# sonoff_DIY_3_gang_Dip_version-V_1_1.net
KiCad netlist of a schematic drawn in EAGLE
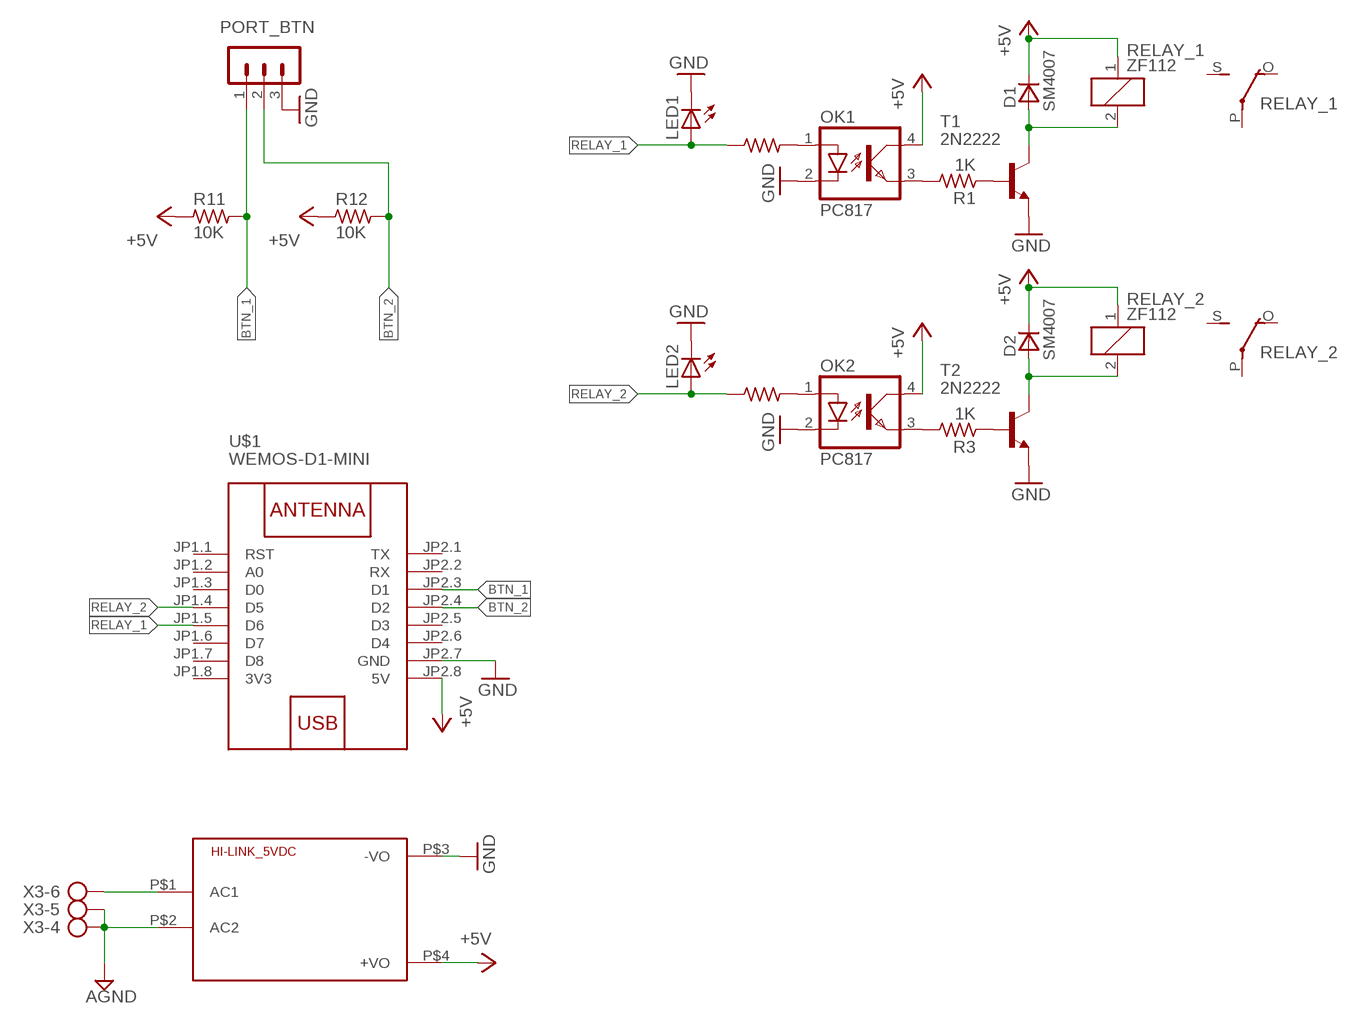
[diagram p0: schematic, sheet 1]

(export (version "E")
  (design (tool "Eeschema 10.0.6"))
  (components
    (comp (ref "D1")
      (value "SM4007")
      (footprint "eagle-import:MELF-MLL41")
      (libsource (lib "eagle-import") (part "SM4007"))
    )
    (comp (ref "D2")
      (value "SM4007")
      (footprint "eagle-import:MELF-MLL41")
      (libsource (lib "eagle-import") (part "SM4007"))
    )
    (comp (ref "HI-LINK_5VDC")
      (value "HLK-PM013W")
      (footprint "eagle-import:HLK-PM01")
      (libsource (lib "eagle-import") (part "HLK-PM013W"))
    )
    (comp (ref "LED1")
      (value "LED3MM")
      (footprint "eagle-import:LED3MM")
      (libsource (lib "eagle-import") (part "LED3MM"))
    )
    (comp (ref "LED2")
      (value "LED3MM")
      (footprint "eagle-import:LED3MM")
      (libsource (lib "eagle-import") (part "LED3MM"))
    )
    (comp (ref "OK1")
      (value "PC817")
      (footprint "eagle-import:DIL04")
      (fields (field (name "MPN") "PC817X4J000F"))
      (libsource (lib "eagle-import") (part "PC817"))
    )
    (comp (ref "OK2")
      (value "PC817")
      (footprint "eagle-import:DIL04")
      (fields (field (name "MPN") "PC817X4J000F"))
      (libsource (lib "eagle-import") (part "PC817"))
    )
    (comp (ref "PORT_BTN")
      (value "MA03-1")
      (footprint "eagle-import:MA03-1")
      (libsource (lib "eagle-import") (part "MA03-1"))
    )
    (comp (ref "R1")
      (value "1K")
      (footprint "eagle-import:R0805")
      (libsource (lib "eagle-import") (part "R_0805"))
    )
    (comp (ref "R2")
      (value "1K")
      (footprint "eagle-import:R0805")
      (libsource (lib "eagle-import") (part "R_0805"))
    )
    (comp (ref "R3")
      (value "1K")
      (footprint "eagle-import:R0805")
      (libsource (lib "eagle-import") (part "R_0805"))
    )
    (comp (ref "R4")
      (value "1K")
      (footprint "eagle-import:R0805")
      (libsource (lib "eagle-import") (part "R_0805"))
    )
    (comp (ref "R11")
      (value "10K")
      (footprint "eagle-import:R0805")
      (libsource (lib "eagle-import") (part "R_0805"))
    )
    (comp (ref "R12")
      (value "10K")
      (footprint "eagle-import:R0805")
      (libsource (lib "eagle-import") (part "R_0805"))
    )
    (comp (ref "RELAY_1")
      (value "ZF112")
      (footprint "eagle-import:ZF112")
      (libsource (lib "eagle-import") (part "ZF112"))
    )
    (comp (ref "RELAY_2")
      (value "ZF112")
      (footprint "eagle-import:ZF112")
      (libsource (lib "eagle-import") (part "ZF112"))
    )
    (comp (ref "T1")
      (value "2N2222")
      (footprint "eagle-import:TO18")
      (libsource (lib "eagle-import") (part "2N2222"))
    )
    (comp (ref "T2")
      (value "2N2222")
      (footprint "eagle-import:TO18")
      (libsource (lib "eagle-import") (part "2N2222"))
    )
    (comp (ref "U$1")
      (value "WEMOS-D1-MINI")
      (footprint "eagle-import:WEMOS-D1-MINI")
      (libsource (lib "eagle-import") (part "WEMOS-D1-MINI"))
    )
    (comp (ref "X3")
      (value "SMKDSP_1,5/6")
      (footprint "eagle-import:SMKDSP_1,5_6")
      (fields (field (name "MF") "FARNELL") (field (name "MPN") "1733619"))
      (libsource (lib "eagle-import") (part "SMKDSP_1,5/6"))
    )
  )
  (nets
    (net (code "1") (name "+5V") (class "Default")
      (node (ref "D1") (pin "C") (pinfunction "C_C") (pintype "passive"))
      (node (ref "D2") (pin "C") (pinfunction "C_C") (pintype "passive"))
      (node (ref "HI-LINK_5VDC") (pin "P$4") (pinfunction "+VO_P$4") (pintype "bidirectional"))
      (node (ref "OK1") (pin "4") (pinfunction "COL_4") (pintype "passive"))
      (node (ref "OK2") (pin "4") (pinfunction "COL_4") (pintype "passive"))
      (node (ref "R11") (pin "1") (pinfunction "1_1") (pintype "passive"))
      (node (ref "R12") (pin "1") (pinfunction "1_1") (pintype "passive"))
      (node (ref "RELAY_1") (pin "1") (pinfunction "1_1") (pintype "passive"))
      (node (ref "RELAY_2") (pin "1") (pinfunction "1_1") (pintype "passive"))
      (node (ref "U$1") (pin "JP2.8") (pinfunction "5V_JP2.8") (pintype "power_in"))
    )
    (net (code "2") (name "/3V3") (class "Default")
      (node (ref "U$1") (pin "JP1.8") (pinfunction "3V3_JP1.8") (pintype "power_in"))
    )
    (net (code "3") (name "AGND") (class "Default")
      (node (ref "HI-LINK_5VDC") (pin "P$2") (pinfunction "AC2_P$2") (pintype "bidirectional"))
      (node (ref "X3") (pin "4") (pinfunction "KL_4") (pintype "passive"))
      (node (ref "X3") (pin "5") (pinfunction "KL_5") (pintype "passive"))
    )
    (net (code "4") (name "BTN_1") (class "Default")
      (node (ref "PORT_BTN") (pin "1") (pinfunction "1_1") (pintype "passive"))
      (node (ref "R11") (pin "2") (pinfunction "2_2") (pintype "passive"))
      (node (ref "U$1") (pin "JP2.3") (pinfunction "D1_JP2.3") (pintype "bidirectional"))
    )
    (net (code "5") (name "BTN_2") (class "Default")
      (node (ref "PORT_BTN") (pin "2") (pinfunction "2_2") (pintype "passive"))
      (node (ref "R12") (pin "2") (pinfunction "2_2") (pintype "passive"))
      (node (ref "U$1") (pin "JP2.4") (pinfunction "D2_JP2.4") (pintype "bidirectional"))
    )
    (net (code "6") (name "GND") (class "Default")
      (node (ref "HI-LINK_5VDC") (pin "P$3") (pinfunction "-VO_P$3") (pintype "bidirectional"))
      (node (ref "LED1") (pin "K") (pinfunction "C_K") (pintype "passive"))
      (node (ref "LED2") (pin "K") (pinfunction "C_K") (pintype "passive"))
      (node (ref "OK1") (pin "2") (pinfunction "C_2") (pintype "passive"))
      (node (ref "OK2") (pin "2") (pinfunction "C_2") (pintype "passive"))
      (node (ref "PORT_BTN") (pin "3") (pinfunction "3_3") (pintype "passive"))
      (node (ref "T1") (pin "1") (pinfunction "E_1") (pintype "passive"))
      (node (ref "T2") (pin "1") (pinfunction "E_1") (pintype "passive"))
      (node (ref "U$1") (pin "JP2.7") (pinfunction "GND_JP2.7") (pintype "power_in"))
    )
    (net (code "7") (name "Net-(HI-LINK_5VDC-AC1)") (class "Default")
      (node (ref "HI-LINK_5VDC") (pin "P$1") (pinfunction "AC1_P$1") (pintype "bidirectional"))
      (node (ref "X3") (pin "6") (pinfunction "KL_6") (pintype "passive"))
    )
    (net (code "8") (name "Net-(OK1-A)") (class "Default")
      (node (ref "OK1") (pin "1") (pinfunction "A_1") (pintype "passive"))
      (node (ref "R2") (pin "1") (pinfunction "1_1") (pintype "passive"))
    )
    (net (code "9") (name "Net-(OK1-EMIT)") (class "Default")
      (node (ref "OK1") (pin "3") (pinfunction "EMIT_3") (pintype "passive"))
      (node (ref "R1") (pin "2") (pinfunction "2_2") (pintype "passive"))
    )
    (net (code "10") (name "Net-(OK2-A)") (class "Default")
      (node (ref "OK2") (pin "1") (pinfunction "A_1") (pintype "passive"))
      (node (ref "R4") (pin "1") (pinfunction "1_1") (pintype "passive"))
    )
    (net (code "11") (name "Net-(OK2-EMIT)") (class "Default")
      (node (ref "OK2") (pin "3") (pinfunction "EMIT_3") (pintype "passive"))
      (node (ref "R3") (pin "2") (pinfunction "2_2") (pintype "passive"))
    )
    (net (code "12") (name "Net-(T1-B)") (class "Default")
      (node (ref "R1") (pin "1") (pinfunction "1_1") (pintype "passive"))
      (node (ref "T1") (pin "2") (pinfunction "B_2") (pintype "passive"))
    )
    (net (code "13") (name "Net-(T1-C)") (class "Default")
      (node (ref "D1") (pin "A") (pinfunction "A_A") (pintype "passive"))
      (node (ref "RELAY_1") (pin "2") (pinfunction "2_2") (pintype "passive"))
      (node (ref "T1") (pin "3") (pinfunction "C_3") (pintype "passive"))
    )
    (net (code "14") (name "Net-(T2-B)") (class "Default")
      (node (ref "R3") (pin "1") (pinfunction "1_1") (pintype "passive"))
      (node (ref "T2") (pin "2") (pinfunction "B_2") (pintype "passive"))
    )
    (net (code "15") (name "Net-(T2-C)") (class "Default")
      (node (ref "D2") (pin "A") (pinfunction "A_A") (pintype "passive"))
      (node (ref "RELAY_2") (pin "2") (pinfunction "2_2") (pintype "passive"))
      (node (ref "T2") (pin "3") (pinfunction "C_3") (pintype "passive"))
    )
    (net (code "16") (name "RELAY_1") (class "Default")
      (node (ref "LED1") (pin "A") (pinfunction "A_A") (pintype "passive"))
      (node (ref "R2") (pin "2") (pinfunction "2_2") (pintype "passive"))
      (node (ref "U$1") (pin "JP1.5") (pinfunction "D6_JP1.5") (pintype "bidirectional"))
    )
    (net (code "17") (name "RELAY_2") (class "Default")
      (node (ref "LED2") (pin "A") (pinfunction "A_A") (pintype "passive"))
      (node (ref "R4") (pin "2") (pinfunction "2_2") (pintype "passive"))
      (node (ref "U$1") (pin "JP1.4") (pinfunction "D5_JP1.4") (pintype "bidirectional"))
    )
    (net (code "18") (name "unconnected-(RELAY_1-PadO)") (class "Default")
      (node (ref "RELAY_1") (pin "O") (pinfunction "O_O") (pintype "passive"))
    )
    (net (code "19") (name "unconnected-(RELAY_1-PadP)") (class "Default")
      (node (ref "RELAY_1") (pin "P") (pinfunction "P_P") (pintype "passive"))
    )
    (net (code "20") (name "unconnected-(RELAY_1-PadS)") (class "Default")
      (node (ref "RELAY_1") (pin "S") (pinfunction "S_S") (pintype "passive"))
    )
    (net (code "21") (name "unconnected-(RELAY_2-PadO)") (class "Default")
      (node (ref "RELAY_2") (pin "O") (pinfunction "O_O") (pintype "passive"))
    )
    (net (code "22") (name "unconnected-(RELAY_2-PadP)") (class "Default")
      (node (ref "RELAY_2") (pin "P") (pinfunction "P_P") (pintype "passive"))
    )
    (net (code "23") (name "unconnected-(RELAY_2-PadS)") (class "Default")
      (node (ref "RELAY_2") (pin "S") (pinfunction "S_S") (pintype "passive"))
    )
    (net (code "24") (name "unconnected-(U$1-A0-PadJP1.2)") (class "Default")
      (node (ref "U$1") (pin "JP1.2") (pinfunction "A0_JP1.2") (pintype "bidirectional"))
    )
    (net (code "25") (name "unconnected-(U$1-D0-PadJP1.3)") (class "Default")
      (node (ref "U$1") (pin "JP1.3") (pinfunction "D0_JP1.3") (pintype "bidirectional"))
    )
    (net (code "26") (name "unconnected-(U$1-D3-PadJP2.5)") (class "Default")
      (node (ref "U$1") (pin "JP2.5") (pinfunction "D3_JP2.5") (pintype "bidirectional"))
    )
    (net (code "27") (name "unconnected-(U$1-D4-PadJP2.6)") (class "Default")
      (node (ref "U$1") (pin "JP2.6") (pinfunction "D4_JP2.6") (pintype "bidirectional"))
    )
    (net (code "28") (name "unconnected-(U$1-D7-PadJP1.6)") (class "Default")
      (node (ref "U$1") (pin "JP1.6") (pinfunction "D7_JP1.6") (pintype "bidirectional"))
    )
    (net (code "29") (name "unconnected-(U$1-D8-PadJP1.7)") (class "Default")
      (node (ref "U$1") (pin "JP1.7") (pinfunction "D8_JP1.7") (pintype "bidirectional"))
    )
    (net (code "30") (name "unconnected-(U$1-RST-PadJP1.1)") (class "Default")
      (node (ref "U$1") (pin "JP1.1") (pinfunction "RST_JP1.1") (pintype "bidirectional"))
    )
    (net (code "31") (name "unconnected-(U$1-RX-PadJP2.2)") (class "Default")
      (node (ref "U$1") (pin "JP2.2") (pinfunction "RX_JP2.2") (pintype "bidirectional"))
    )
    (net (code "32") (name "unconnected-(U$1-TX-PadJP2.1)") (class "Default")
      (node (ref "U$1") (pin "JP2.1") (pinfunction "TX_JP2.1") (pintype "bidirectional"))
    )
  )
)
